# Sheet1.net
KiCad netlist of a schematic drawn in Altium Designer
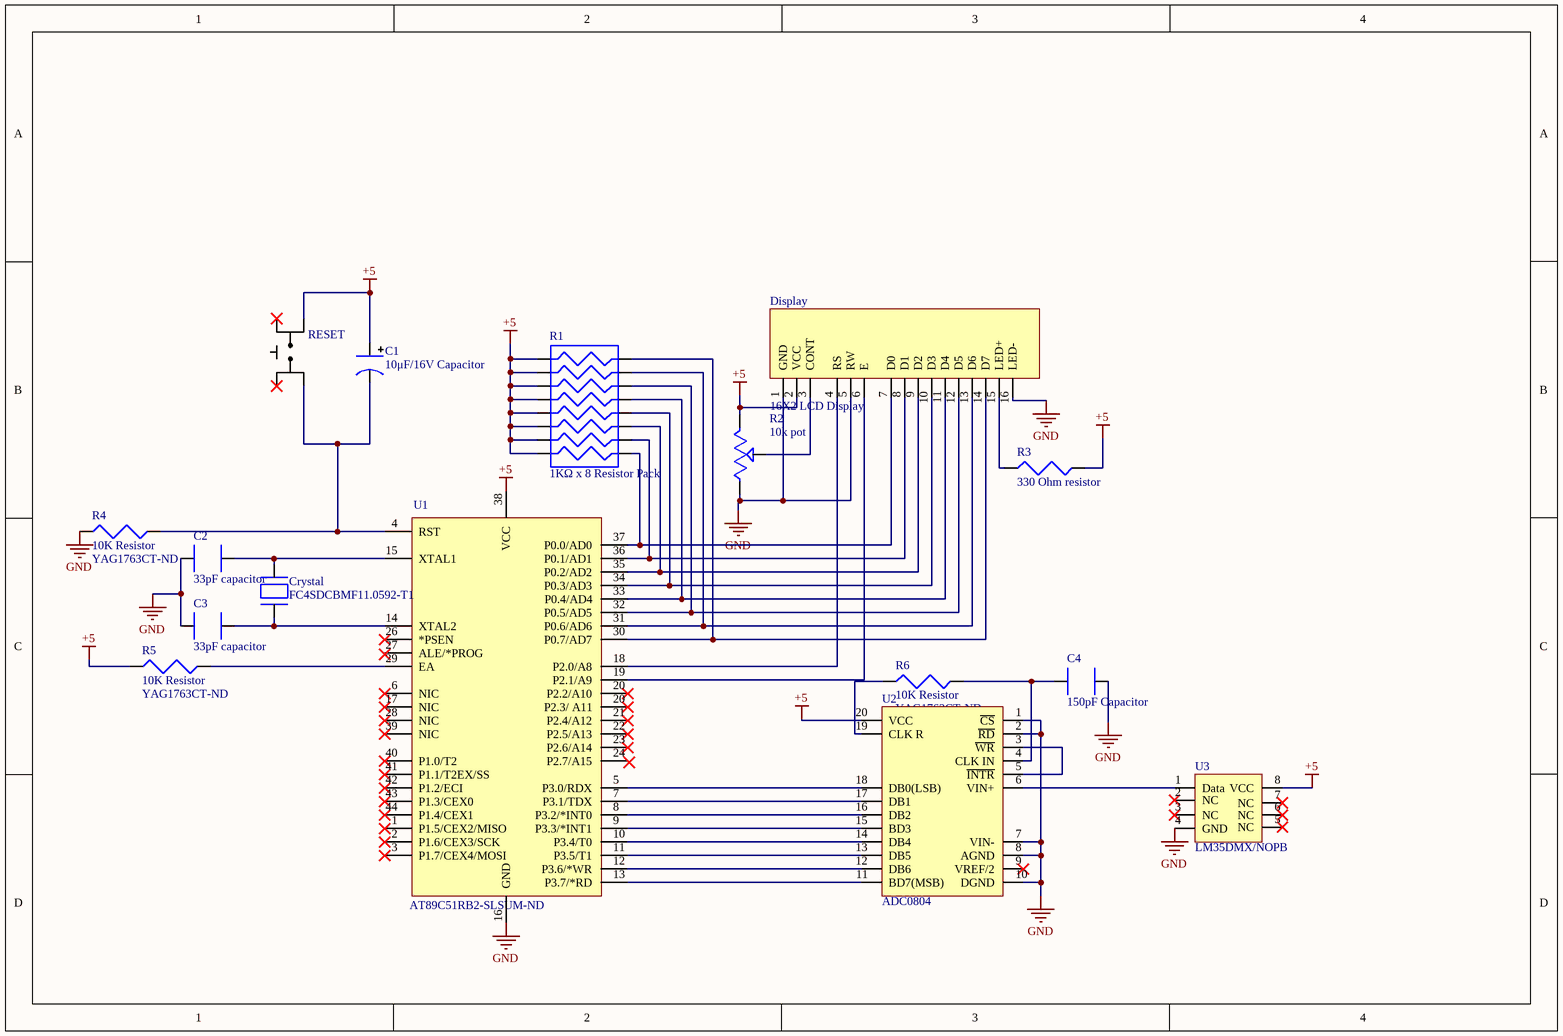
[diagram p0: Sheet1.SchDoc]

(export (version "E")
  (design (tool "Eeschema 10.0.6"))
  (components
    (comp (ref "C1")
      (value "10μF/16V Capacitor")
      (footprint "10µf/16v Capacitor")
      (description "Multilayer Ceramic Capacitors MLCC - SMD/SMT 10uF 16V X5R 10%")
      (fields
        (field (name "MANUFACTURER") "Yageo")
        (field (name "MANUFACTURER PART NUMBER") "CC0805KKX5R7BB106")
      )
      (libsource (lib "0805 SMD resistor") (part "10μF/16V Capacitor"))
    )
    (comp (ref "C2")
      (value "33pF capacitor")
      (footprint "33pF Capacitor")
      (description "Cap Ceramic 33pF 50V C0G 5% SMD 0402 125C Paper T/R")
      (fields
        (field (name "MANUFACTURER") "Samsung")
        (field (name "MANUFACTURER PART NUMBER") "CL05C330JB5NNNC")
      )
      (libsource (lib "0805 SMD resistor") (part "smd 33pF capacitor"))
    )
    (comp (ref "C3")
      (value "33pF capacitor")
      (footprint "33pF Capacitor")
      (description "Cap Ceramic 33pF 50V C0G 5% SMD 0402 125C Paper T/R")
      (fields
        (field (name "MANUFACTURER") "Samsung")
        (field (name "MANUFACTURER PART NUMBER") "CL05C330JB5NNNC")
      )
      (libsource (lib "0805 SMD resistor") (part "smd 33pF capacitor"))
    )
    (comp (ref "C4")
      (value "150pF Capacitor")
      (footprint "150pF Capacitor")
      (description "CAP CER 150PF 250V NPO 0603")
      (fields
        (field (name "MANUFACTURER") "Yageo")
        (field (name "MANUFACTURER PART NUMBER") "AC0603JRNPOYBN151")
      )
      (libsource (lib "0805 SMD resistor") (part "150pF Capacitor"))
    )
    (comp (ref "Crystal")
      (value "FC4SDCBMF11.0592-T1")
      (footprint "Crystal 11.0592MHz")
      (description "Crystal 11.0592MHz ±30ppm (Tol) ±50ppm (Stability) 20pF FUND 60Ohm 2-Pin HC-49/SDLF SMD T/R")
      (fields (field (name "MANUFACTURER") "Fox Electronics"))
      (libsource (lib "0805 SMD resistor") (part "FC4SDCBMF11.0592-T1"))
    )
    (comp (ref "Display")
      (value "16X2 LCD Display")
      (footprint "16X2 LCD Display")
      (description "LCD Graphic Display Modules & Accessories FSTN (+) 80.0 x 36.0")
      (fields
        (field (name "MANUFACTURER") "Newhaven Display")
        (field (name "MANUFACTURER PART NUMBER") "NHD-14432WG-BTFH-V#T")
      )
      (libsource (lib "0805 SMD resistor") (part "16X2 LCD Display"))
    )
    (comp (ref "R1")
      (value "1KΩ x 8 Resistor Pack")
      (footprint "1KO x 8 Resistor Pack")
      (description "RES ARRAY 8 RES 1K OHM 16SOIC")
      (fields
        (field (name "MANUFACTURER") "Vishay Dale Thin Film")
        (field (name "MANUFACTURER PART NUMBER") "NOMCT16031001AT1")
      )
      (libsource (lib "0805 SMD resistor") (part "1KΩ x 8 Resistor Pack"))
    )
    (comp (ref "R2")
      (value "10k pot")
      (footprint "10k pot")
      (fields
        (field (name "MANUFACTURER") "Alps Electric")
        (field (name "MANUFACTURER PART NUMBER") "RK09L1120A2S")
        (field (name "TOLERANCE") "20%")
      )
      (libsource (lib "0805 SMD resistor") (part "10k pot"))
    )
    (comp (ref "R3")
      (value "330 Ohm resistor")
      (footprint "330O Resistor")
      (description "YAGEO   RC0805JR-07330RL   THICK FILM RESISTOR, 330 OHM, 125mW, 5%, FULL REEL")
      (fields
        (field (name "MANUFACTURER") "Yageo")
        (field (name "MANUFACTURER PART NUMBER") "RL0805FR-7W0R33L")
      )
      (libsource (lib "0805 SMD resistor") (part "0805SMD 330resistor"))
    )
    (comp (ref "R4")
      (value "10K Resistor")
      (footprint "10KO Resistor")
      (fields (field (name "SUPPLIER PART NUMBER 1") "YAG1763CT-ND"))
      (libsource (lib "0805 SMD resistor") (part "0805 SMD 10k resistor"))
    )
    (comp (ref "R5")
      (value "10K Resistor")
      (footprint "10KO Resistor")
      (fields (field (name "SUPPLIER PART NUMBER 1") "YAG1763CT-ND"))
      (libsource (lib "0805 SMD resistor") (part "0805 SMD 10k resistor"))
    )
    (comp (ref "R6")
      (value "10K Resistor")
      (footprint "10KO Resistor")
      (fields (field (name "SUPPLIER PART NUMBER 1") "YAG1763CT-ND"))
      (libsource (lib "0805 SMD resistor") (part "0805 SMD 10k resistor"))
    )
    (comp (ref "RESET")
      (value "TL3305AF260QG")
      (footprint "Reset")
      (description "Tactile Switches 6mm SMT Gull Wing 5mm Act Height")
      (fields (field (name "MANUFACTURER") "E-Switch"))
      (libsource (lib "0805 SMD resistor") (part "TL3305AF260QG"))
    )
    (comp (ref "U1")
      (value "AT89C51RB2-SLSUM")
      (footprint "AT89C51 (8051 Microcontroller)")
      (description "MCU 8-bit AT89 80C51 CISC 32KB Flash 3.3V/5V 44-Pin VQFP Tray")
      (fields
        (field (name "MANUFACTURER") "Microchip / Atmel")
        (field (name "SUPPLIER PART NUMBER 1") "AT89C51RB2-SLSUM-ND")
      )
      (libsource (lib "0805 SMD resistor") (part "AT89C51RB2-SLSUM"))
    )
    (comp (ref "U2")
      (value "ADC0804")
      (footprint "ADC0804")
      (fields
        (field (name "MANUFACTURER") "TI National Semiconductor")
        (field (name "MANUFACTURER PART NUMBER") "ADC0804LCWM/NOPB")
      )
      (libsource (lib "0805 SMD resistor") (part "ADC0804"))
    )
    (comp (ref "U3")
      (value "LM35DMX/NOPB")
      (footprint "LM35DMX")
      (description "SENSOR ANALOG 0C-100C 8SOIC")
      (fields (field (name "MANUFACTURER") "TI National Semiconductor"))
      (libsource (lib "0805 SMD resistor") (part "LM35DMX/NOPB"))
    )
  )
  (nets
    (net (code "1") (name "+5") (class "Default")
      (node (ref "C1") (pin "1") (pinfunction "1_1") (pintype "passive"))
      (node (ref "Display") (pin "2") (pinfunction "VCC_2") (pintype "passive"))
      (node (ref "R1") (pin "1") (pinfunction "1_1") (pintype "passive"))
      (node (ref "R1") (pin "2") (pinfunction "2_2") (pintype "passive"))
      (node (ref "R1") (pin "3") (pinfunction "3_3") (pintype "passive"))
      (node (ref "R1") (pin "4") (pinfunction "4_4") (pintype "passive"))
      (node (ref "R1") (pin "5") (pinfunction "5_5") (pintype "passive"))
      (node (ref "R1") (pin "6") (pinfunction "6_6") (pintype "passive"))
      (node (ref "R1") (pin "7") (pinfunction "7_7") (pintype "passive"))
      (node (ref "R1") (pin "8") (pinfunction "8_8") (pintype "passive"))
      (node (ref "R2") (pin "2") (pinfunction "2_2") (pintype "passive"))
      (node (ref "R3") (pin "2") (pinfunction "2_2") (pintype "passive"))
      (node (ref "R5") (pin "1") (pinfunction "1_1") (pintype "passive"))
      (node (ref "RESET") (pin "3") (pinfunction "3_3") (pintype "passive"))
      (node (ref "U1") (pin "38") (pinfunction "VCC_38") (pintype "passive"))
      (node (ref "U2") (pin "20") (pinfunction "VCC_20") (pintype "passive"))
      (node (ref "U3") (pin "8") (pinfunction "VCC_8") (pintype "passive"))
    )
    (net (code "2") (name "GND") (class "Default")
      (node (ref "C2") (pin "1") (pinfunction "1_1") (pintype "passive"))
      (node (ref "C3") (pin "1") (pinfunction "1_1") (pintype "passive"))
      (node (ref "C4") (pin "2") (pinfunction "2_2") (pintype "passive"))
      (node (ref "Display") (pin "1") (pinfunction "GND_1") (pintype "passive"))
      (node (ref "Display") (pin "16") (pinfunction "LED-_16") (pintype "passive"))
      (node (ref "Display") (pin "5") (pinfunction "RW_5") (pintype "passive"))
      (node (ref "R2") (pin "1") (pinfunction "1_1") (pintype "passive"))
      (node (ref "R4") (pin "1") (pinfunction "1_1") (pintype "passive"))
      (node (ref "U1") (pin "16") (pinfunction "GND_16") (pintype "passive"))
      (node (ref "U2") (pin "1") (pinfunction "~{CS}_1") (pintype "passive"))
      (node (ref "U2") (pin "10") (pinfunction "DGND_10") (pintype "passive"))
      (node (ref "U2") (pin "2") (pinfunction "~{RD}_2") (pintype "passive"))
      (node (ref "U2") (pin "7") (pinfunction "VIN-_7") (pintype "passive"))
      (node (ref "U2") (pin "8") (pinfunction "AGND_8") (pintype "passive"))
      (node (ref "U3") (pin "4") (pinfunction "GND_4") (pintype "passive"))
    )
    (net (code "3") (name "Net-(Display-CONT)") (class "Default")
      (node (ref "Display") (pin "3") (pinfunction "CONT_3") (pintype "passive"))
      (node (ref "R2") (pin "3") (pinfunction "3_3") (pintype "passive"))
    )
    (net (code "4") (name "Net-(Display-D0)") (class "Default")
      (node (ref "Display") (pin "7") (pinfunction "D0_7") (pintype "passive"))
      (node (ref "R1") (pin "9") (pinfunction "9_9") (pintype "passive"))
      (node (ref "U1") (pin "37") (pinfunction "P0.0/AD0_37") (pintype "passive"))
    )
    (net (code "5") (name "Net-(Display-D1)") (class "Default")
      (node (ref "Display") (pin "8") (pinfunction "D1_8") (pintype "passive"))
      (node (ref "R1") (pin "10") (pinfunction "10_10") (pintype "passive"))
      (node (ref "U1") (pin "36") (pinfunction "P0.1/AD1_36") (pintype "passive"))
    )
    (net (code "6") (name "Net-(Display-D2)") (class "Default")
      (node (ref "Display") (pin "9") (pinfunction "D2_9") (pintype "passive"))
      (node (ref "R1") (pin "11") (pinfunction "11_11") (pintype "passive"))
      (node (ref "U1") (pin "35") (pinfunction "P0.2/AD2_35") (pintype "passive"))
    )
    (net (code "7") (name "Net-(Display-D3)") (class "Default")
      (node (ref "Display") (pin "10") (pinfunction "D3_10") (pintype "passive"))
      (node (ref "R1") (pin "12") (pinfunction "12_12") (pintype "passive"))
      (node (ref "U1") (pin "34") (pinfunction "P0.3/AD3_34") (pintype "passive"))
    )
    (net (code "8") (name "Net-(Display-D4)") (class "Default")
      (node (ref "Display") (pin "11") (pinfunction "D4_11") (pintype "passive"))
      (node (ref "R1") (pin "13") (pinfunction "13_13") (pintype "passive"))
      (node (ref "U1") (pin "33") (pinfunction "P0.4/AD4_33") (pintype "passive"))
    )
    (net (code "9") (name "Net-(Display-D5)") (class "Default")
      (node (ref "Display") (pin "12") (pinfunction "D5_12") (pintype "passive"))
      (node (ref "R1") (pin "14") (pinfunction "14_14") (pintype "passive"))
      (node (ref "U1") (pin "32") (pinfunction "P0.5/AD5_32") (pintype "passive"))
    )
    (net (code "10") (name "Net-(Display-D6)") (class "Default")
      (node (ref "Display") (pin "13") (pinfunction "D6_13") (pintype "passive"))
      (node (ref "R1") (pin "15") (pinfunction "15_15") (pintype "passive"))
      (node (ref "U1") (pin "31") (pinfunction "P0.6/AD6_31") (pintype "passive"))
    )
    (net (code "11") (name "Net-(Display-D7)") (class "Default")
      (node (ref "Display") (pin "14") (pinfunction "D7_14") (pintype "passive"))
      (node (ref "R1") (pin "16") (pinfunction "16_16") (pintype "passive"))
      (node (ref "U1") (pin "30") (pinfunction "P0.7/AD7_30") (pintype "passive"))
    )
    (net (code "12") (name "Net-(Display-E)") (class "Default")
      (node (ref "Display") (pin "6") (pinfunction "E_6") (pintype "passive"))
      (node (ref "U1") (pin "19") (pinfunction "P2.1/A9_19") (pintype "passive"))
    )
    (net (code "13") (name "Net-(Display-LED+)") (class "Default")
      (node (ref "Display") (pin "15") (pinfunction "LED+_15") (pintype "passive"))
      (node (ref "R3") (pin "1") (pinfunction "1_1") (pintype "passive"))
    )
    (net (code "14") (name "Net-(Display-RS)") (class "Default")
      (node (ref "Display") (pin "4") (pinfunction "RS_4") (pintype "passive"))
      (node (ref "U1") (pin "18") (pinfunction "P2.0/A8_18") (pintype "passive"))
    )
    (net (code "15") (name "Net-(U1-EA)") (class "Default")
      (node (ref "R5") (pin "2") (pinfunction "2_2") (pintype "passive"))
      (node (ref "U1") (pin "29") (pinfunction "EA_29") (pintype "passive"))
    )
    (net (code "16") (name "Net-(U1-P3.0{slash}RDX)") (class "Default")
      (node (ref "U1") (pin "5") (pinfunction "P3.0/RDX_5") (pintype "passive"))
      (node (ref "U2") (pin "18") (pinfunction "DB0(LSB)_18") (pintype "passive"))
    )
    (net (code "17") (name "Net-(U1-P3.1{slash}TDX)") (class "Default")
      (node (ref "U1") (pin "7") (pinfunction "P3.1/TDX_7") (pintype "passive"))
      (node (ref "U2") (pin "17") (pinfunction "DB1_17") (pintype "passive"))
    )
    (net (code "18") (name "Net-(U1-P3.2{slash}*INT0)") (class "Default")
      (node (ref "U1") (pin "8") (pinfunction "P3.2/*INT0_8") (pintype "passive"))
      (node (ref "U2") (pin "16") (pinfunction "DB2_16") (pintype "passive"))
    )
    (net (code "19") (name "Net-(U1-P3.3{slash}*INT1)") (class "Default")
      (node (ref "U1") (pin "9") (pinfunction "P3.3/*INT1_9") (pintype "passive"))
      (node (ref "U2") (pin "15") (pinfunction "BD3_15") (pintype "passive"))
    )
    (net (code "20") (name "Net-(U1-P3.4{slash}T0)") (class "Default")
      (node (ref "U1") (pin "10") (pinfunction "P3.4/T0_10") (pintype "passive"))
      (node (ref "U2") (pin "14") (pinfunction "DB4_14") (pintype "passive"))
    )
    (net (code "21") (name "Net-(U1-P3.5{slash}T1)") (class "Default")
      (node (ref "U1") (pin "11") (pinfunction "P3.5/T1_11") (pintype "passive"))
      (node (ref "U2") (pin "13") (pinfunction "DB5_13") (pintype "passive"))
    )
    (net (code "22") (name "Net-(U1-P3.6{slash}*WR)") (class "Default")
      (node (ref "U1") (pin "12") (pinfunction "P3.6/*WR_12") (pintype "passive"))
      (node (ref "U2") (pin "12") (pinfunction "DB6_12") (pintype "passive"))
    )
    (net (code "23") (name "Net-(U1-P3.7{slash}*RD)") (class "Default")
      (node (ref "U1") (pin "13") (pinfunction "P3.7/*RD_13") (pintype "passive"))
      (node (ref "U2") (pin "11") (pinfunction "BD7(MSB)_11") (pintype "passive"))
    )
    (net (code "24") (name "Net-(U1-RST)") (class "Default")
      (node (ref "C1") (pin "2") (pinfunction "2_2") (pintype "passive"))
      (node (ref "R4") (pin "2") (pinfunction "2_2") (pintype "passive"))
      (node (ref "RESET") (pin "2") (pinfunction "2_2") (pintype "passive"))
      (node (ref "U1") (pin "4") (pinfunction "RST_4") (pintype "passive"))
    )
    (net (code "25") (name "Net-(U1-XTAL1)") (class "Default")
      (node (ref "C2") (pin "2") (pinfunction "2_2") (pintype "passive"))
      (node (ref "Crystal") (pin "2") (pinfunction "2_2") (pintype "passive"))
      (node (ref "U1") (pin "15") (pinfunction "XTAL1_15") (pintype "passive"))
    )
    (net (code "26") (name "Net-(U1-XTAL2)") (class "Default")
      (node (ref "C3") (pin "2") (pinfunction "2_2") (pintype "passive"))
      (node (ref "Crystal") (pin "1") (pinfunction "1_1") (pintype "passive"))
      (node (ref "U1") (pin "14") (pinfunction "XTAL2_14") (pintype "passive"))
    )
    (net (code "27") (name "Net-(U2-CLK_IN)") (class "Default")
      (node (ref "C4") (pin "1") (pinfunction "1_1") (pintype "passive"))
      (node (ref "R6") (pin "2") (pinfunction "2_2") (pintype "passive"))
      (node (ref "U2") (pin "4") (pinfunction "CLK_IN_4") (pintype "passive"))
    )
    (net (code "28") (name "Net-(U2-CLK_R)") (class "Default")
      (node (ref "R6") (pin "1") (pinfunction "1_1") (pintype "passive"))
      (node (ref "U2") (pin "19") (pinfunction "CLK_R_19") (pintype "passive"))
    )
    (net (code "29") (name "Net-(U2-VIN+)") (class "Default")
      (node (ref "U2") (pin "6") (pinfunction "VIN+_6") (pintype "passive"))
      (node (ref "U3") (pin "1") (pinfunction "Data_1") (pintype "passive"))
    )
    (net (code "30") (name "Net-(U2-~{INTR})") (class "Default")
      (node (ref "U2") (pin "3") (pinfunction "~{WR}_3") (pintype "passive"))
      (node (ref "U2") (pin "5") (pinfunction "~{INTR}_5") (pintype "passive"))
    )
    (net (code "31") (name "unconnected-(RESET-Pad1)") (class "Default")
      (node (ref "RESET") (pin "1") (pinfunction "1_1") (pintype "passive+no_connect"))
    )
    (net (code "32") (name "unconnected-(RESET-Pad4)") (class "Default")
      (node (ref "RESET") (pin "4") (pinfunction "4_4") (pintype "passive+no_connect"))
    )
    (net (code "33") (name "unconnected-(U1-*PSEN-Pad26)") (class "Default")
      (node (ref "U1") (pin "26") (pinfunction "*PSEN_26") (pintype "passive+no_connect"))
    )
    (net (code "34") (name "unconnected-(U1-ALE{slash}*PROG-Pad27)") (class "Default")
      (node (ref "U1") (pin "27") (pinfunction "ALE/*PROG_27") (pintype "passive"))
    )
    (net (code "35") (name "unconnected-(U1-NIC-Pad6)") (class "Default")
      (node (ref "U1") (pin "6") (pinfunction "NIC_6") (pintype "passive+no_connect"))
    )
    (net (code "36") (name "unconnected-(U1-NIC-Pad17)") (class "Default")
      (node (ref "U1") (pin "17") (pinfunction "NIC_17") (pintype "passive+no_connect"))
    )
    (net (code "37") (name "unconnected-(U1-NIC-Pad28)") (class "Default")
      (node (ref "U1") (pin "28") (pinfunction "NIC_28") (pintype "passive+no_connect"))
    )
    (net (code "38") (name "unconnected-(U1-NIC-Pad39)") (class "Default")
      (node (ref "U1") (pin "39") (pinfunction "NIC_39") (pintype "passive+no_connect"))
    )
    (net (code "39") (name "unconnected-(U1-P1.0{slash}T2-Pad40)") (class "Default")
      (node (ref "U1") (pin "40") (pinfunction "P1.0/T2_40") (pintype "passive+no_connect"))
    )
    (net (code "40") (name "unconnected-(U1-P1.1{slash}T2EX{slash}SS-Pad41)") (class "Default")
      (node (ref "U1") (pin "41") (pinfunction "P1.1/T2EX/SS_41") (pintype "passive+no_connect"))
    )
    (net (code "41") (name "unconnected-(U1-P1.2{slash}ECI-Pad42)") (class "Default")
      (node (ref "U1") (pin "42") (pinfunction "P1.2/ECI_42") (pintype "passive+no_connect"))
    )
    (net (code "42") (name "unconnected-(U1-P1.3{slash}CEX0-Pad43)") (class "Default")
      (node (ref "U1") (pin "43") (pinfunction "P1.3/CEX0_43") (pintype "passive+no_connect"))
    )
    (net (code "43") (name "unconnected-(U1-P1.4{slash}CEX1-Pad44)") (class "Default")
      (node (ref "U1") (pin "44") (pinfunction "P1.4/CEX1_44") (pintype "passive+no_connect"))
    )
    (net (code "44") (name "unconnected-(U1-P1.5{slash}CEX2{slash}MISO-Pad1)") (class "Default")
      (node (ref "U1") (pin "1") (pinfunction "P1.5/CEX2/MISO_1") (pintype "passive+no_connect"))
    )
    (net (code "45") (name "unconnected-(U1-P1.6{slash}CEX3{slash}SCK-Pad2)") (class "Default")
      (node (ref "U1") (pin "2") (pinfunction "P1.6/CEX3/SCK_2") (pintype "passive+no_connect"))
    )
    (net (code "46") (name "unconnected-(U1-P1.7{slash}CEX4{slash}MOSI-Pad3)") (class "Default")
      (node (ref "U1") (pin "3") (pinfunction "P1.7/CEX4/MOSI_3") (pintype "passive+no_connect"))
    )
    (net (code "47") (name "unconnected-(U1-P2.2{slash}A10-Pad20)") (class "Default")
      (node (ref "U1") (pin "20") (pinfunction "P2.2/A10_20") (pintype "passive+no_connect"))
    )
    (net (code "48") (name "unconnected-(U1-P2.3{slash}_A11-Pad20)") (class "Default")
      (node (ref "U1") (pin "20") (pinfunction "P2.3/_A11_20") (pintype "passive+no_connect"))
    )
    (net (code "49") (name "unconnected-(U1-P2.4{slash}A12-Pad21)") (class "Default")
      (node (ref "U1") (pin "21") (pinfunction "P2.4/A12_21") (pintype "passive+no_connect"))
    )
    (net (code "50") (name "unconnected-(U1-P2.5{slash}A13-Pad22)") (class "Default")
      (node (ref "U1") (pin "22") (pinfunction "P2.5/A13_22") (pintype "passive+no_connect"))
    )
    (net (code "51") (name "unconnected-(U1-P2.6{slash}A14-Pad23)") (class "Default")
      (node (ref "U1") (pin "23") (pinfunction "P2.6/A14_23") (pintype "passive+no_connect"))
    )
    (net (code "52") (name "unconnected-(U1-P2.7{slash}A15-Pad24)") (class "Default")
      (node (ref "U1") (pin "24") (pinfunction "P2.7/A15_24") (pintype "passive"))
    )
    (net (code "53") (name "unconnected-(U2-VREF{slash}2-Pad9)") (class "Default")
      (node (ref "U2") (pin "9") (pinfunction "VREF/2_9") (pintype "passive+no_connect"))
    )
    (net (code "54") (name "unconnected-(U3-NC-Pad2)") (class "Default")
      (node (ref "U3") (pin "2") (pinfunction "NC_2") (pintype "passive+no_connect"))
    )
    (net (code "55") (name "unconnected-(U3-NC-Pad3)") (class "Default")
      (node (ref "U3") (pin "3") (pinfunction "NC_3") (pintype "passive+no_connect"))
    )
    (net (code "56") (name "unconnected-(U3-NC-Pad5)") (class "Default")
      (node (ref "U3") (pin "5") (pinfunction "NC_5") (pintype "passive+no_connect"))
    )
    (net (code "57") (name "unconnected-(U3-NC-Pad6)") (class "Default")
      (node (ref "U3") (pin "6") (pinfunction "NC_6") (pintype "passive+no_connect"))
    )
    (net (code "58") (name "unconnected-(U3-NC-Pad7)") (class "Default")
      (node (ref "U3") (pin "7") (pinfunction "NC_7") (pintype "passive+no_connect"))
    )
  )
)
